# X10_PowerBoard_RevB.net
KiCad netlist of a schematic drawn in EAGLE
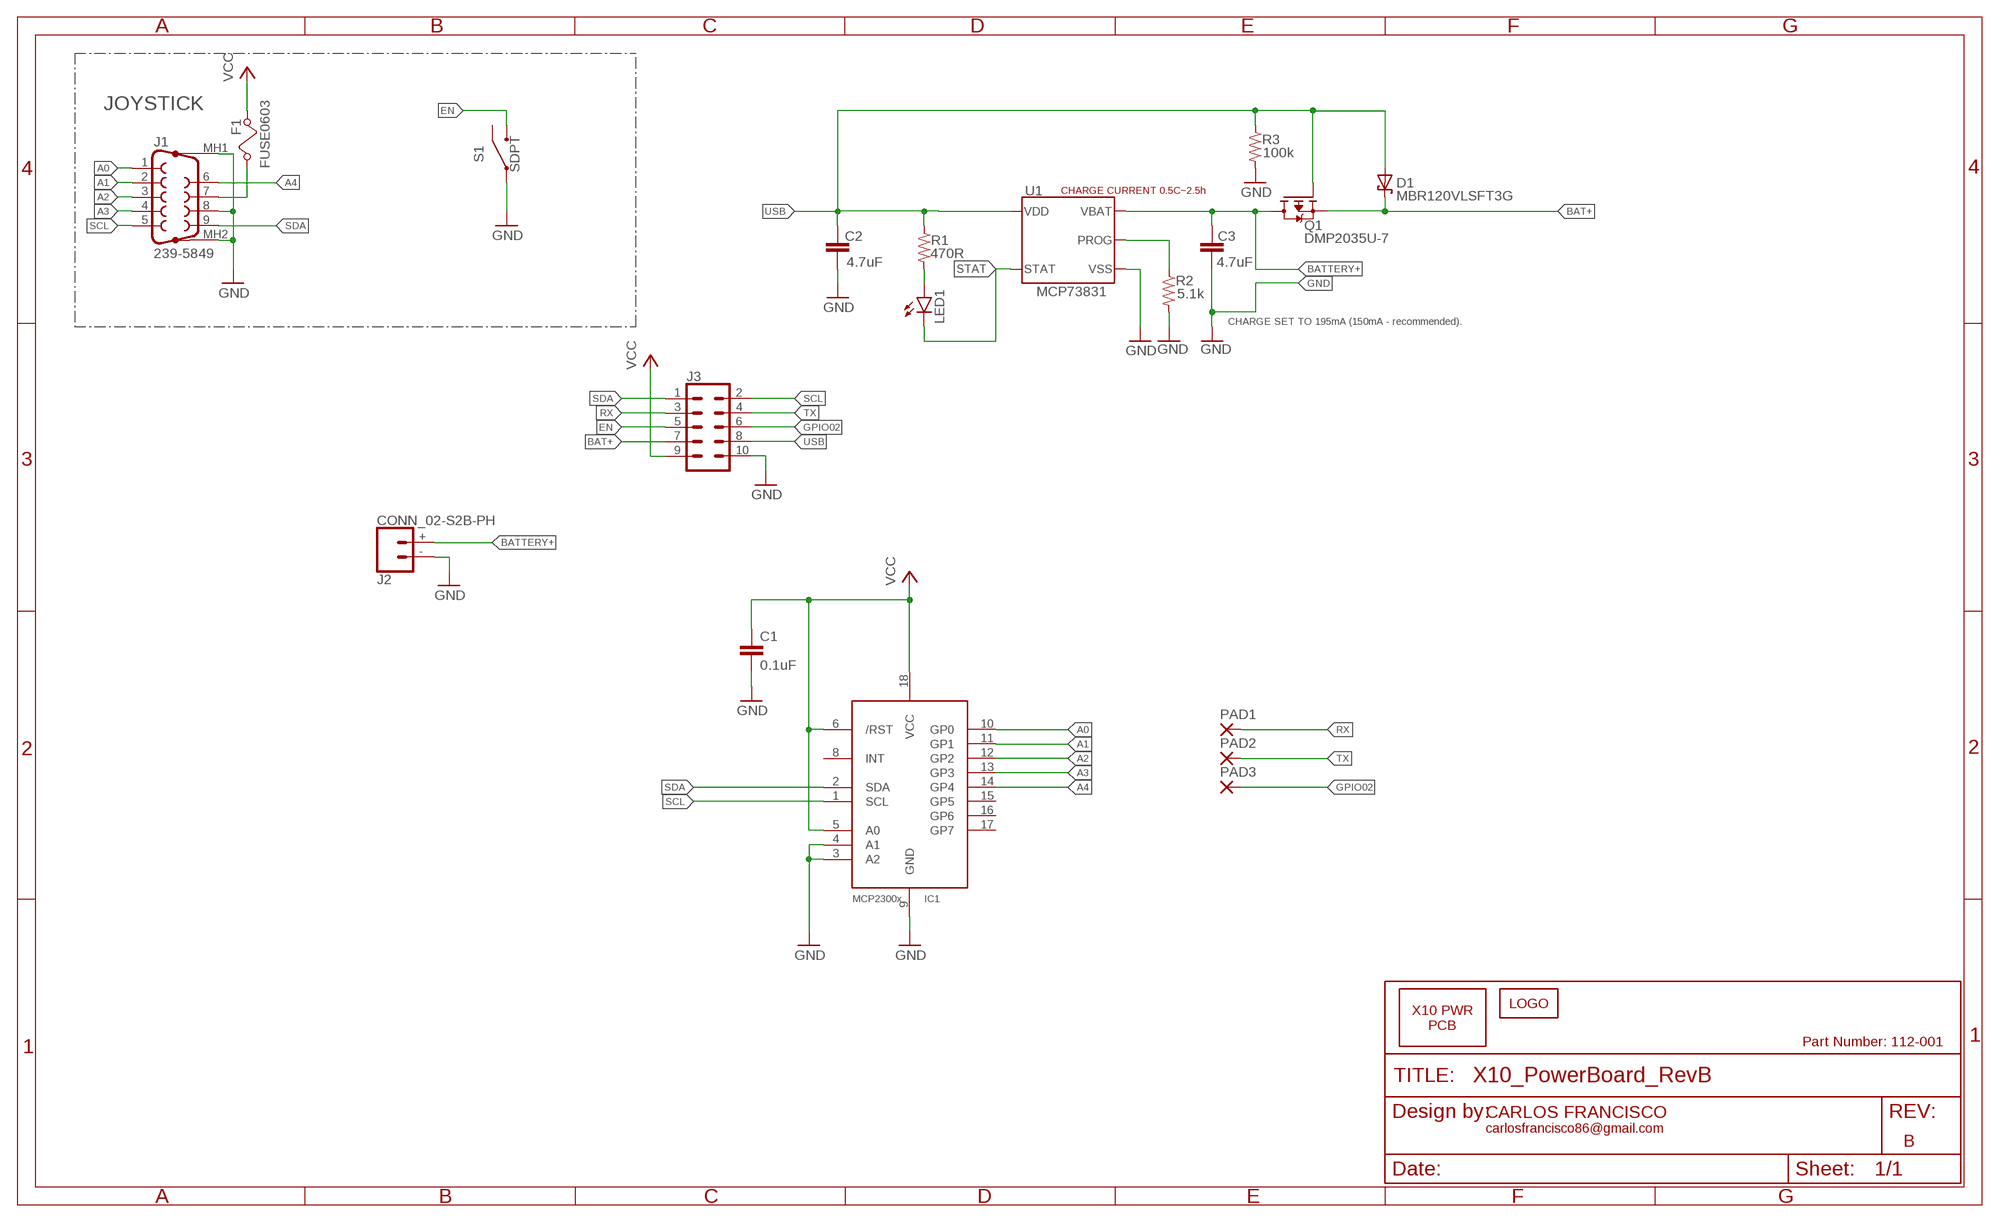
[diagram p0: schematic, sheet 1]

(export (version "E")
  (design (tool "Eeschema 10.0.6"))
  (components
    (comp (ref "C1")
      (value "0.1uF")
      (footprint "eagle-import:C0603")
      (libsource (lib "eagle-import") (part "C-EUC0603"))
    )
    (comp (ref "C2")
      (value "4.7uF")
      (footprint "eagle-import:CAPC1608X85")
      (fields (field (name "MFR") "Samsung Electro-Mechanics"))
      (libsource (lib "eagle-import") (part "C-0603-4.7UF-10V-X5R"))
    )
    (comp (ref "C3")
      (value "4.7uF")
      (footprint "eagle-import:CAPC1608X85")
      (fields (field (name "MFR") "Samsung Electro-Mechanics"))
      (libsource (lib "eagle-import") (part "C-0603-4.7UF-10V-X5R"))
    )
    (comp (ref "D1")
      (value "MBR120VLSFT3G")
      (footprint "eagle-import:SODFL3616X98N")
      (fields (field (name "MFR") "On Semiconductor"))
      (libsource (lib "eagle-import") (part "DIODE-SCHOTTKYSOD-123FL-20V-1A"))
    )
    (comp (ref "F1")
      (value "FUSE0603")
      (footprint "eagle-import:FUSC1607X75N")
      (libsource (lib "eagle-import") (part "FUSE0603"))
    )
    (comp (ref "IC1")
      (value "MCP23008/P")
      (footprint "eagle-import:DIL18")
      (libsource (lib "eagle-import") (part "MCP23008/P"))
    )
    (comp (ref "J1")
      (value "239-5849")
      (footprint "eagle-import:DB9_PLUG_SLOT")
      (fields (field (name "MFR") "RS Pro"))
      (libsource (lib "eagle-import") (part "DB9_MALE-SLOTS"))
    )
    (comp (ref "J2")
      (value "CONN_02-S2B-PH")
      (footprint "eagle-import:S2B-PH-RA")
      (libsource (lib "eagle-import") (part "CONN_02-S2B-PH"))
    )
    (comp (ref "J3")
      (value "CONN2_05-HEADER")
      (footprint "eagle-import:2X5_HEADER")
      (libsource (lib "eagle-import") (part "CONN2_05-HEADER"))
    )
    (comp (ref "LED1")
      (value "LEDSML0603")
      (footprint "eagle-import:SML0603")
      (libsource (lib "eagle-import") (part "LEDSML0603"))
    )
    (comp (ref "LOGO1")
      (value "LOGO-10MM")
      (footprint "eagle-import:LOGO_10MM")
      (libsource (lib "eagle-import") (part "LOGO-10MM"))
    )
    (comp (ref "PAD1")
      (value "1,6/0,8")
      (footprint "eagle-import:1,6_0,8")
      (libsource (lib "eagle-import") (part "1,6/0,8"))
    )
    (comp (ref "PAD2")
      (value "1,6/0,8")
      (footprint "eagle-import:1,6_0,8")
      (libsource (lib "eagle-import") (part "1,6/0,8"))
    )
    (comp (ref "PAD3")
      (value "1,6/0,8")
      (footprint "eagle-import:1,6_0,8")
      (libsource (lib "eagle-import") (part "1,6/0,8"))
    )
    (comp (ref "PCB1")
      (value "X10_PWR_PCB-X10_PWR_PCB")
      (footprint "eagle-import:X10_POWER_PCB")
      (libsource (lib "eagle-import") (part "X10_PWR_PCB-X10_PWR_PCB"))
    )
    (comp (ref "Q1")
      (value "DMP2035U-7")
      (footprint "eagle-import:SOT95P230X110-3N")
      (fields (field (name "MFR") "Diodes Incorporated"))
      (libsource (lib "eagle-import") (part "P-MOSFET-SOT323-DMP2035U-7"))
    )
    (comp (ref "R1")
      (value "470R")
      (footprint "eagle-import:RESC1608X60")
      (fields (field (name "MFR") "Yageo"))
      (libsource (lib "eagle-import") (part "R-BACKUP-0603-470R-1%"))
    )
    (comp (ref "R2")
      (value "5.1k")
      (footprint "eagle-import:RESC1608X60")
      (fields (field (name "MFR") "Yageo"))
      (libsource (lib "eagle-import") (part "R-0603-5.1K-1%"))
    )
    (comp (ref "R3")
      (value "100k")
      (footprint "eagle-import:RESC1608X60")
      (fields (field (name "MFR") "Yageo"))
      (libsource (lib "eagle-import") (part "R-0603-100K-1%"))
    )
    (comp (ref "S1")
      (value "SDPT")
      (footprint "eagle-import:OS102011MA1QN1")
      (fields (field (name "MFR") "C & K COMPONENTS"))
      (libsource (lib "eagle-import") (part "SLIDE_SWITCH"))
    )
    (comp (ref "U1")
      (value "MCP73831")
      (footprint "eagle-import:SOT23-5P95_270X145L35X35N")
      (fields (field (name "MFR") "Microchip"))
      (libsource (lib "eagle-import") (part "MCP73831"))
    )
  )
  (nets
    (net (code "1") (name "A0") (class "Default")
      (node (ref "IC1") (pin "10") (pinfunction "GP0_10") (pintype "bidirectional"))
      (node (ref "J1") (pin "1") (pinfunction "1_1") (pintype "passive"))
    )
    (net (code "2") (name "A1") (class "Default")
      (node (ref "IC1") (pin "11") (pinfunction "GP1_11") (pintype "bidirectional"))
      (node (ref "J1") (pin "2") (pinfunction "2_2") (pintype "passive"))
    )
    (net (code "3") (name "A2") (class "Default")
      (node (ref "IC1") (pin "12") (pinfunction "GP2_12") (pintype "bidirectional"))
      (node (ref "J1") (pin "3") (pinfunction "3_3") (pintype "passive"))
    )
    (net (code "4") (name "A3") (class "Default")
      (node (ref "IC1") (pin "13") (pinfunction "GP3_13") (pintype "bidirectional"))
      (node (ref "J1") (pin "4") (pinfunction "4_4") (pintype "passive"))
    )
    (net (code "5") (name "A4") (class "Default")
      (node (ref "IC1") (pin "14") (pinfunction "GP4_14") (pintype "bidirectional"))
      (node (ref "J1") (pin "6") (pinfunction "6_6") (pintype "passive"))
    )
    (net (code "6") (name "BAT+") (class "Default")
      (node (ref "D1") (pin "K") (pinfunction "C_K") (pintype "passive"))
      (node (ref "J3") (pin "7") (pinfunction "7_7") (pintype "passive"))
      (node (ref "Q1") (pin "2") (pinfunction "S_2") (pintype "passive"))
    )
    (net (code "7") (name "BATTERY+") (class "Default")
      (node (ref "C3") (pin "1") (pinfunction "1_1") (pintype "passive"))
      (node (ref "J2") (pin "+") (pinfunction "1_+") (pintype "passive"))
      (node (ref "Q1") (pin "3") (pinfunction "D_3") (pintype "passive"))
      (node (ref "U1") (pin "3") (pinfunction "VBAT_3") (pintype "bidirectional"))
    )
    (net (code "8") (name "EN") (class "Default")
      (node (ref "J3") (pin "5") (pinfunction "5_5") (pintype "passive"))
      (node (ref "S1") (pin "1") (pinfunction "1_1") (pintype "passive"))
    )
    (net (code "9") (name "GND") (class "Default")
      (node (ref "C1") (pin "2") (pinfunction "2_2") (pintype "passive"))
      (node (ref "C2") (pin "2") (pinfunction "2_2") (pintype "passive"))
      (node (ref "C3") (pin "2") (pinfunction "2_2") (pintype "passive"))
      (node (ref "IC1") (pin "3") (pinfunction "A2_3") (pintype "input"))
      (node (ref "IC1") (pin "4") (pinfunction "A1_4") (pintype "input"))
      (node (ref "IC1") (pin "9") (pinfunction "GND_9") (pintype "power_in"))
      (node (ref "J1") (pin "8") (pinfunction "8_8") (pintype "passive"))
      (node (ref "J1") (pin "MH1") (pinfunction "G1_MH1") (pintype "passive"))
      (node (ref "J1") (pin "MH2") (pinfunction "G2_MH2") (pintype "passive"))
      (node (ref "J2") (pin "-") (pinfunction "2_-") (pintype "passive"))
      (node (ref "J3") (pin "10") (pinfunction "10_10") (pintype "passive"))
      (node (ref "R2") (pin "1") (pinfunction "1_1") (pintype "passive"))
      (node (ref "R3") (pin "1") (pinfunction "1_1") (pintype "passive"))
      (node (ref "S1") (pin "2") (pinfunction "2_2") (pintype "passive"))
      (node (ref "U1") (pin "2") (pinfunction "VSS_2") (pintype "power_in"))
    )
    (net (code "10") (name "GPIO02") (class "Default")
      (node (ref "J3") (pin "6") (pinfunction "6_6") (pintype "passive"))
      (node (ref "PAD3") (pin "1") (pinfunction "P_1") (pintype "passive"))
    )
    (net (code "11") (name "Net-(F1-Pad1)") (class "Default")
      (node (ref "F1") (pin "1") (pinfunction "1_1") (pintype "passive"))
      (node (ref "J1") (pin "7") (pinfunction "7_7") (pintype "passive"))
    )
    (net (code "12") (name "Net-(LED1-PadA)") (class "Default")
      (node (ref "LED1") (pin "A") (pinfunction "A_A") (pintype "passive"))
      (node (ref "R1") (pin "1") (pinfunction "1_1") (pintype "passive"))
    )
    (net (code "13") (name "Net-(U1-PROG)") (class "Default")
      (node (ref "R2") (pin "2") (pinfunction "2_2") (pintype "passive"))
      (node (ref "U1") (pin "5") (pinfunction "PROG_5") (pintype "input"))
    )
    (net (code "14") (name "RX") (class "Default")
      (node (ref "J3") (pin "3") (pinfunction "3_3") (pintype "passive"))
      (node (ref "PAD1") (pin "1") (pinfunction "P_1") (pintype "passive"))
    )
    (net (code "15") (name "SCL") (class "Default")
      (node (ref "IC1") (pin "1") (pinfunction "SCL_1") (pintype "bidirectional"))
      (node (ref "J1") (pin "5") (pinfunction "5_5") (pintype "passive"))
      (node (ref "J3") (pin "2") (pinfunction "2_2") (pintype "passive"))
    )
    (net (code "16") (name "SDA") (class "Default")
      (node (ref "IC1") (pin "2") (pinfunction "SDA_2") (pintype "bidirectional"))
      (node (ref "J1") (pin "9") (pinfunction "9_9") (pintype "passive"))
      (node (ref "J3") (pin "1") (pinfunction "1_1") (pintype "passive"))
    )
    (net (code "17") (name "STAT") (class "Default")
      (node (ref "LED1") (pin "C") (pinfunction "C_C") (pintype "passive"))
      (node (ref "U1") (pin "1") (pinfunction "STAT_1") (pintype "output"))
    )
    (net (code "18") (name "TX") (class "Default")
      (node (ref "J3") (pin "4") (pinfunction "4_4") (pintype "passive"))
      (node (ref "PAD2") (pin "1") (pinfunction "P_1") (pintype "passive"))
    )
    (net (code "19") (name "USB") (class "Default")
      (node (ref "C2") (pin "1") (pinfunction "1_1") (pintype "passive"))
      (node (ref "D1") (pin "A") (pinfunction "A_A") (pintype "passive"))
      (node (ref "J3") (pin "8") (pinfunction "8_8") (pintype "passive"))
      (node (ref "Q1") (pin "1") (pinfunction "G_1") (pintype "passive"))
      (node (ref "R1") (pin "2") (pinfunction "2_2") (pintype "passive"))
      (node (ref "R3") (pin "2") (pinfunction "2_2") (pintype "passive"))
      (node (ref "U1") (pin "4") (pinfunction "VDD_4") (pintype "input"))
    )
    (net (code "20") (name "VCC") (class "Default")
      (node (ref "C1") (pin "1") (pinfunction "1_1") (pintype "passive"))
      (node (ref "F1") (pin "2") (pinfunction "2_2") (pintype "passive"))
      (node (ref "IC1") (pin "18") (pinfunction "VCC_18") (pintype "power_in"))
      (node (ref "IC1") (pin "5") (pinfunction "A0_5") (pintype "input"))
      (node (ref "IC1") (pin "6") (pinfunction "/RST_6") (pintype "input"))
      (node (ref "J3") (pin "9") (pinfunction "9_9") (pintype "passive"))
    )
    (net (code "21") (name "unconnected-(IC1-GP5-Pad15)") (class "Default")
      (node (ref "IC1") (pin "15") (pinfunction "GP5_15") (pintype "bidirectional"))
    )
    (net (code "22") (name "unconnected-(IC1-GP6-Pad16)") (class "Default")
      (node (ref "IC1") (pin "16") (pinfunction "GP6_16") (pintype "bidirectional"))
    )
    (net (code "23") (name "unconnected-(IC1-GP7-Pad17)") (class "Default")
      (node (ref "IC1") (pin "17") (pinfunction "GP7_17") (pintype "bidirectional"))
    )
    (net (code "24") (name "unconnected-(IC1-INT-Pad8)") (class "Default")
      (node (ref "IC1") (pin "8") (pinfunction "INT_8") (pintype "output"))
    )
    (net (code "25") (name "unconnected-(S1-Pad3)") (class "Default")
      (node (ref "S1") (pin "3") (pinfunction "3_3") (pintype "passive"))
    )
  )
)
